# SCH_Power-Pcb-With-100v-3300uf_2024-05-0.net
KiCad netlist of a schematic drawn in EasyEDA
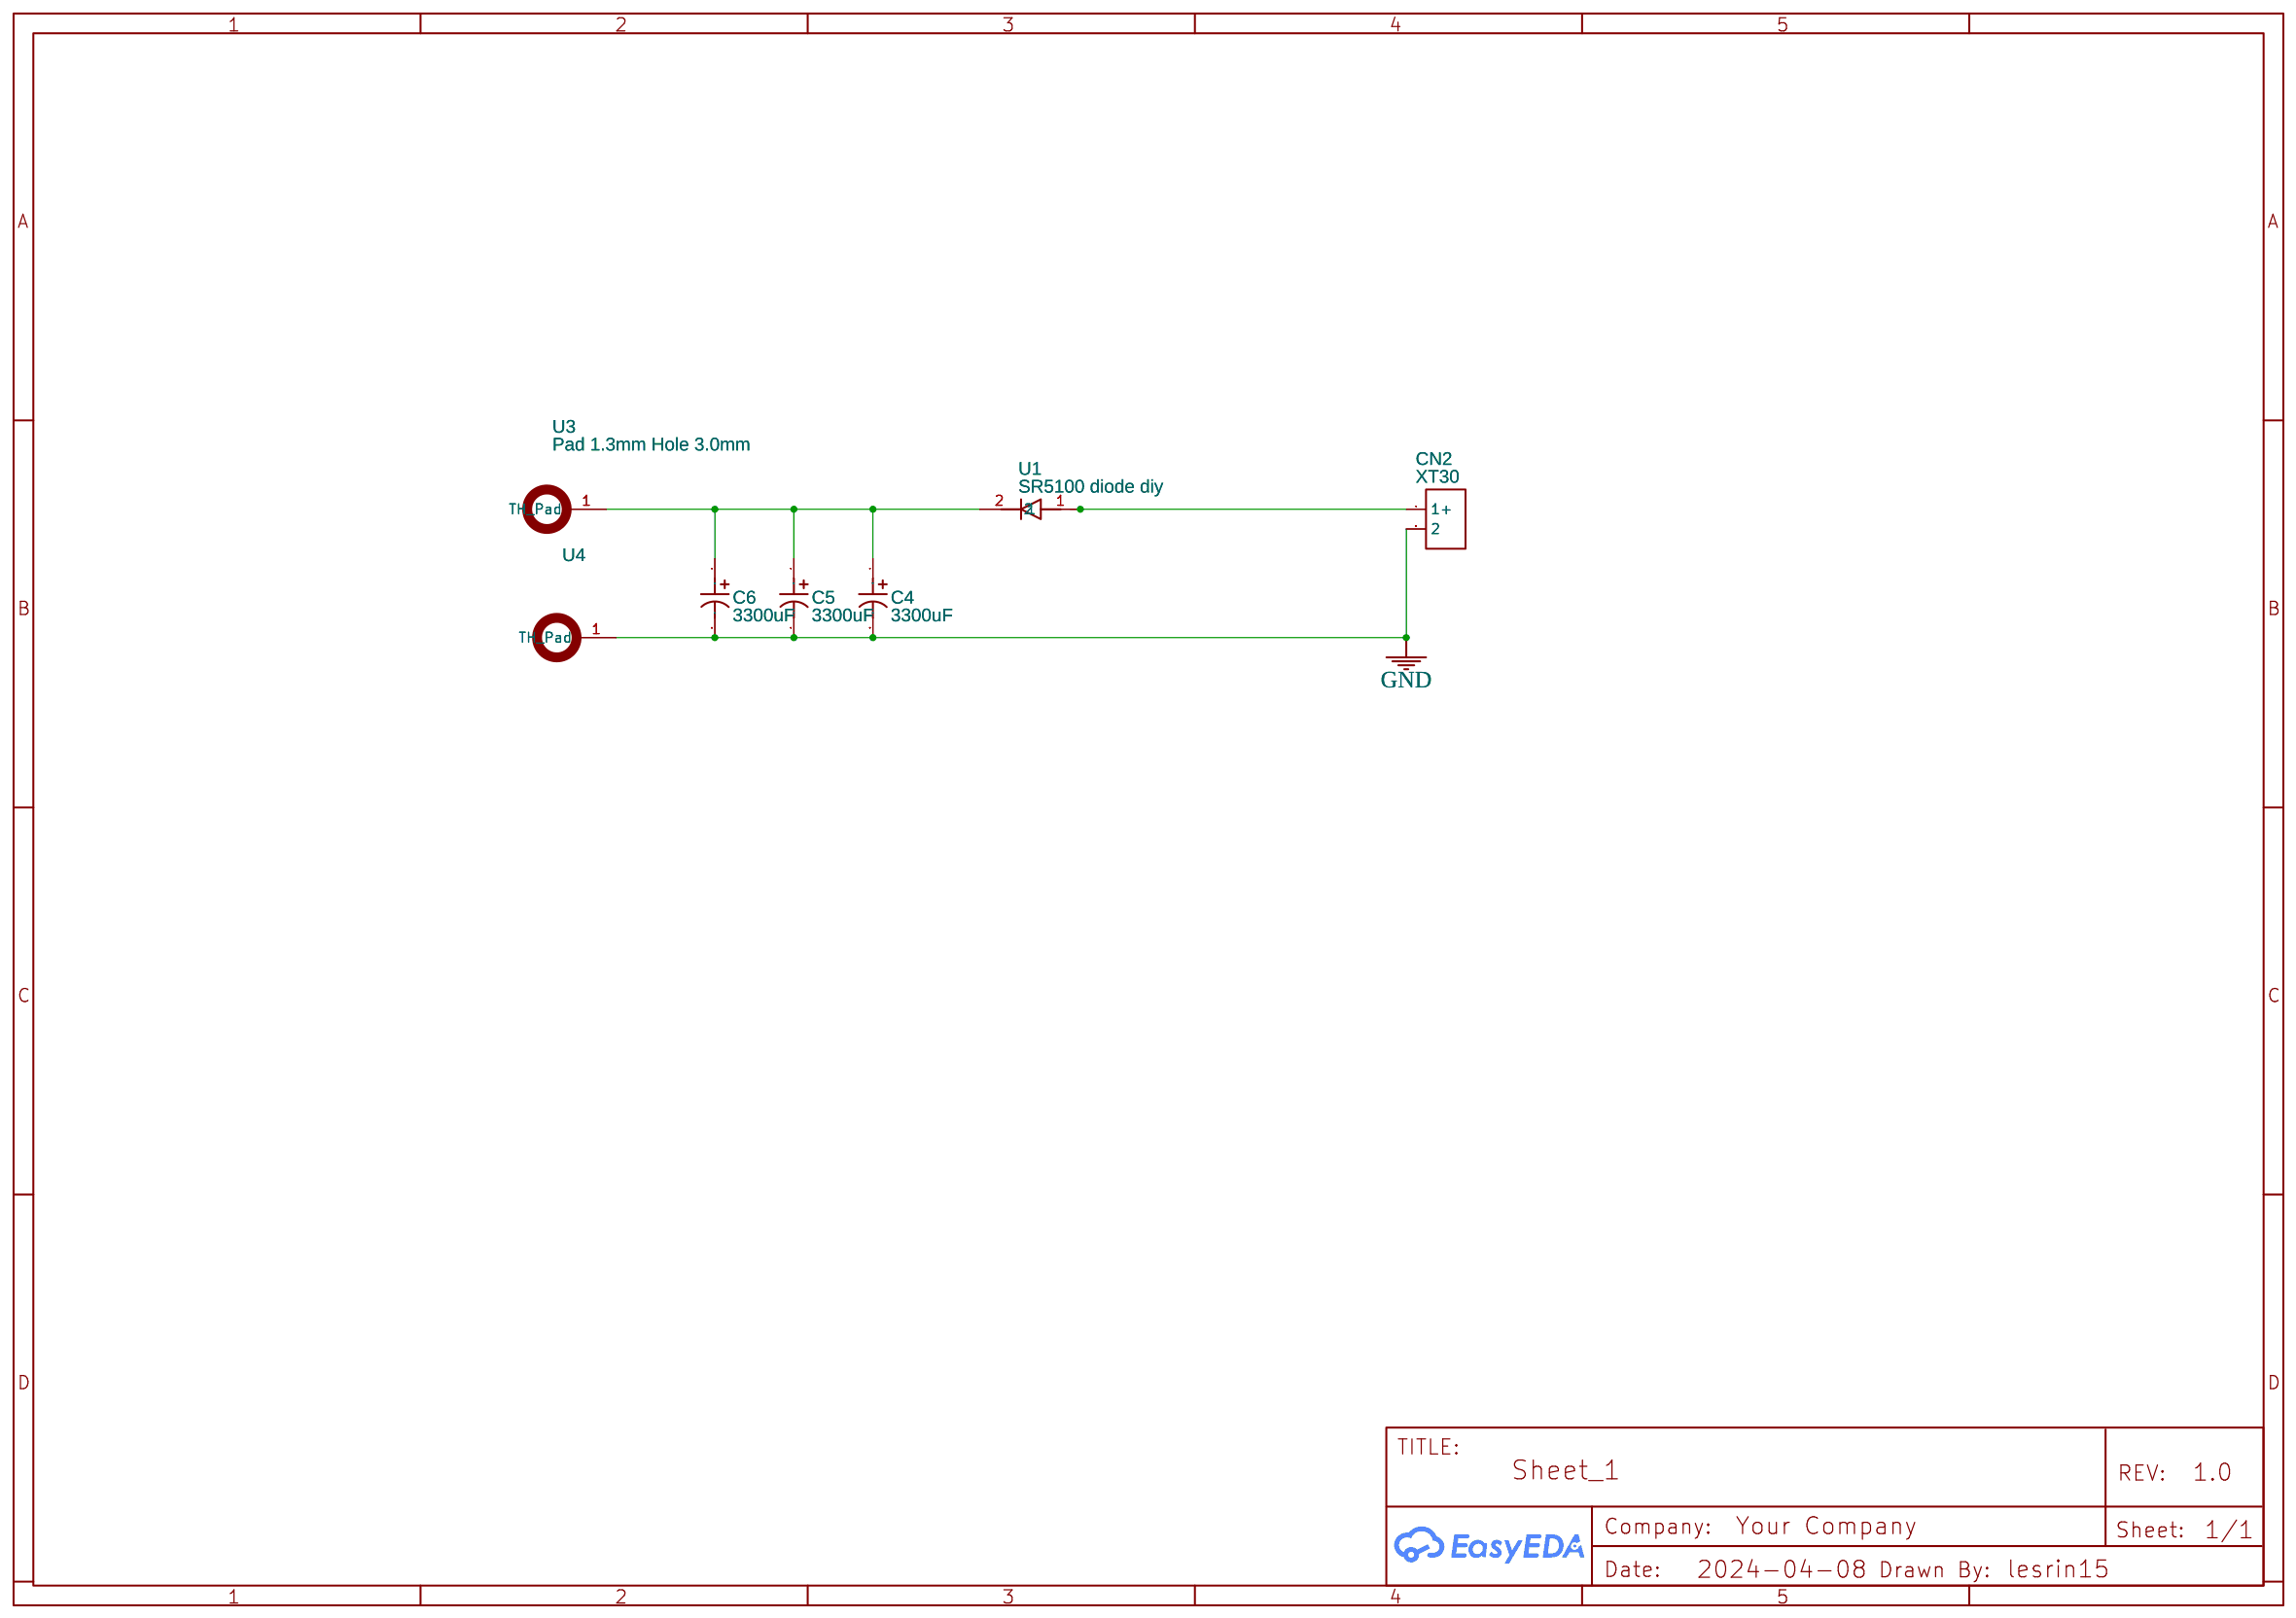
[diagram p0: schematic sheet]

(export (version "E")
  (design (tool "Eeschema 10.0.6"))
  (components
    (comp (ref "C4")
      (value "3300uF")
      (fields (field (name "Manufacturer Part") "CG332MHG40B") (field (name "Manufacturer") "TWBOR(伯鸿)"))
      (libsource (lib "") (part "CG332MHG40B"))
    )
    (comp (ref "C5")
      (value "3300uF")
      (fields (field (name "Manufacturer Part") "CG332MHG40B") (field (name "Manufacturer") "TWBOR(伯鸿)"))
      (libsource (lib "") (part "CG332MHG40B"))
    )
    (comp (ref "C6")
      (value "3300uF")
      (fields (field (name "Manufacturer Part") "CG332MHG40B") (field (name "Manufacturer") "TWBOR(伯鸿)"))
      (libsource (lib "") (part "CG332MHG40B"))
    )
    (comp (ref "CN2")
      (value "XT30")
      (fields (field (name "Manufacturer Part") "XT30UPB-F"))
      (libsource (lib "") (part "XT30UPB-F ARUN"))
    )
    (comp (ref "U1") (value "SR5100 diode diy") (libsource (lib "") (part "SR5100 diode diy")))
    (comp (ref "U3") (value "Pad 1.3mm Hole 3.0mm") (libsource (lib "") (part "Pad 1.7mm Hole 3.0mm")))
    (comp (ref "U4") (value "Pad 1.3mm Hole 3.0mm") (libsource (lib "") (part "Pad 1.7mm Hole 3.0mm")))
  )
  (nets
    (net (code "1") (name "GND") (class "Default")
      (node (ref "C4") (pin "2") (pinfunction "2_2") (pintype "input"))
      (node (ref "C5") (pin "2") (pinfunction "2_2") (pintype "input"))
      (node (ref "C6") (pin "2") (pinfunction "2_2") (pintype "input"))
      (node (ref "CN2") (pin "2") (pinfunction "2_2") (pintype "unspecified"))
      (node (ref "U4") (pin "1") (pinfunction "TH_Pad_1") (pintype "unspecified"))
    )
    (net (code "2") (name "Net-(CN2-1+)") (class "Default")
      (node (ref "CN2") (pin "1") (pinfunction "1+_1") (pintype "unspecified"))
      (node (ref "U1") (pin "1") (pinfunction "1_1") (pintype "unspecified"))
    )
    (net (code "3") (name "Net-(U3-TH_Pad)") (class "Default")
      (node (ref "C4") (pin "1") (pinfunction "1_1") (pintype "input"))
      (node (ref "C5") (pin "1") (pinfunction "1_1") (pintype "input"))
      (node (ref "C6") (pin "1") (pinfunction "1_1") (pintype "input"))
      (node (ref "U1") (pin "2") (pinfunction "2_2") (pintype "unspecified"))
      (node (ref "U3") (pin "1") (pinfunction "TH_Pad_1") (pintype "unspecified"))
    )
  )
)
